# E-07_CPU_MISC.net
KiCad netlist of a schematic drawn in Altium Designer
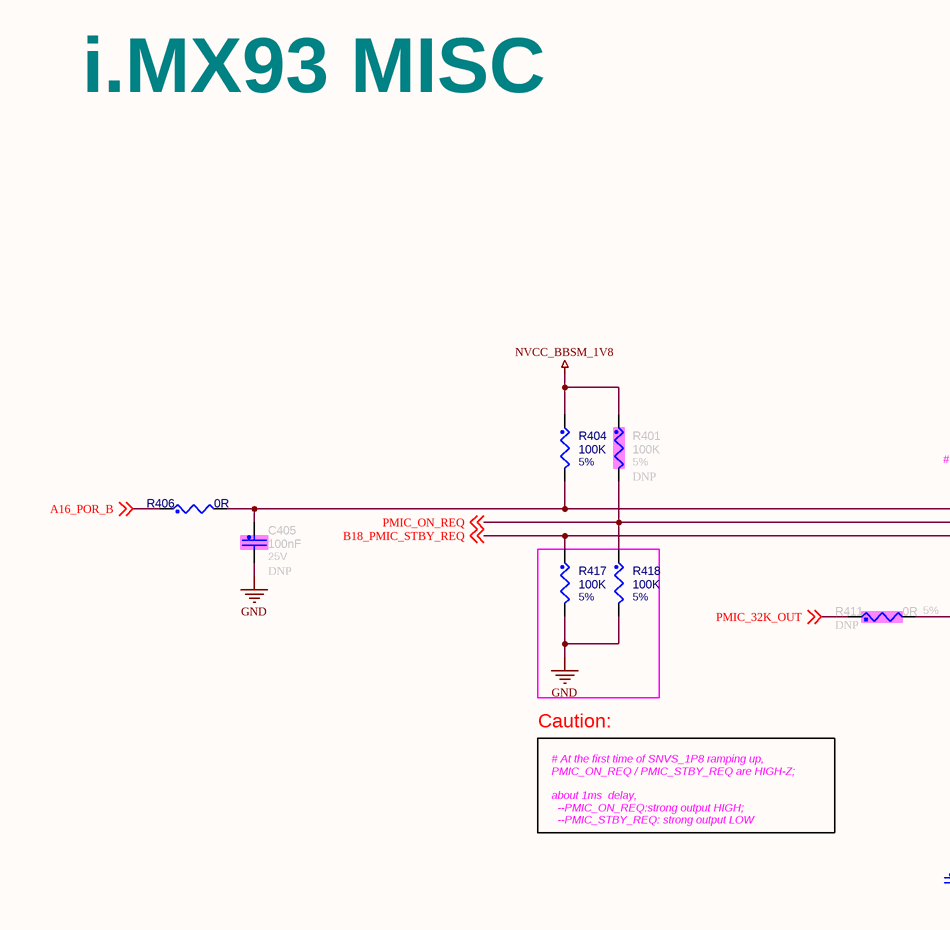
[diagram p0: E-07 CPU MISC.SchDoc, left]
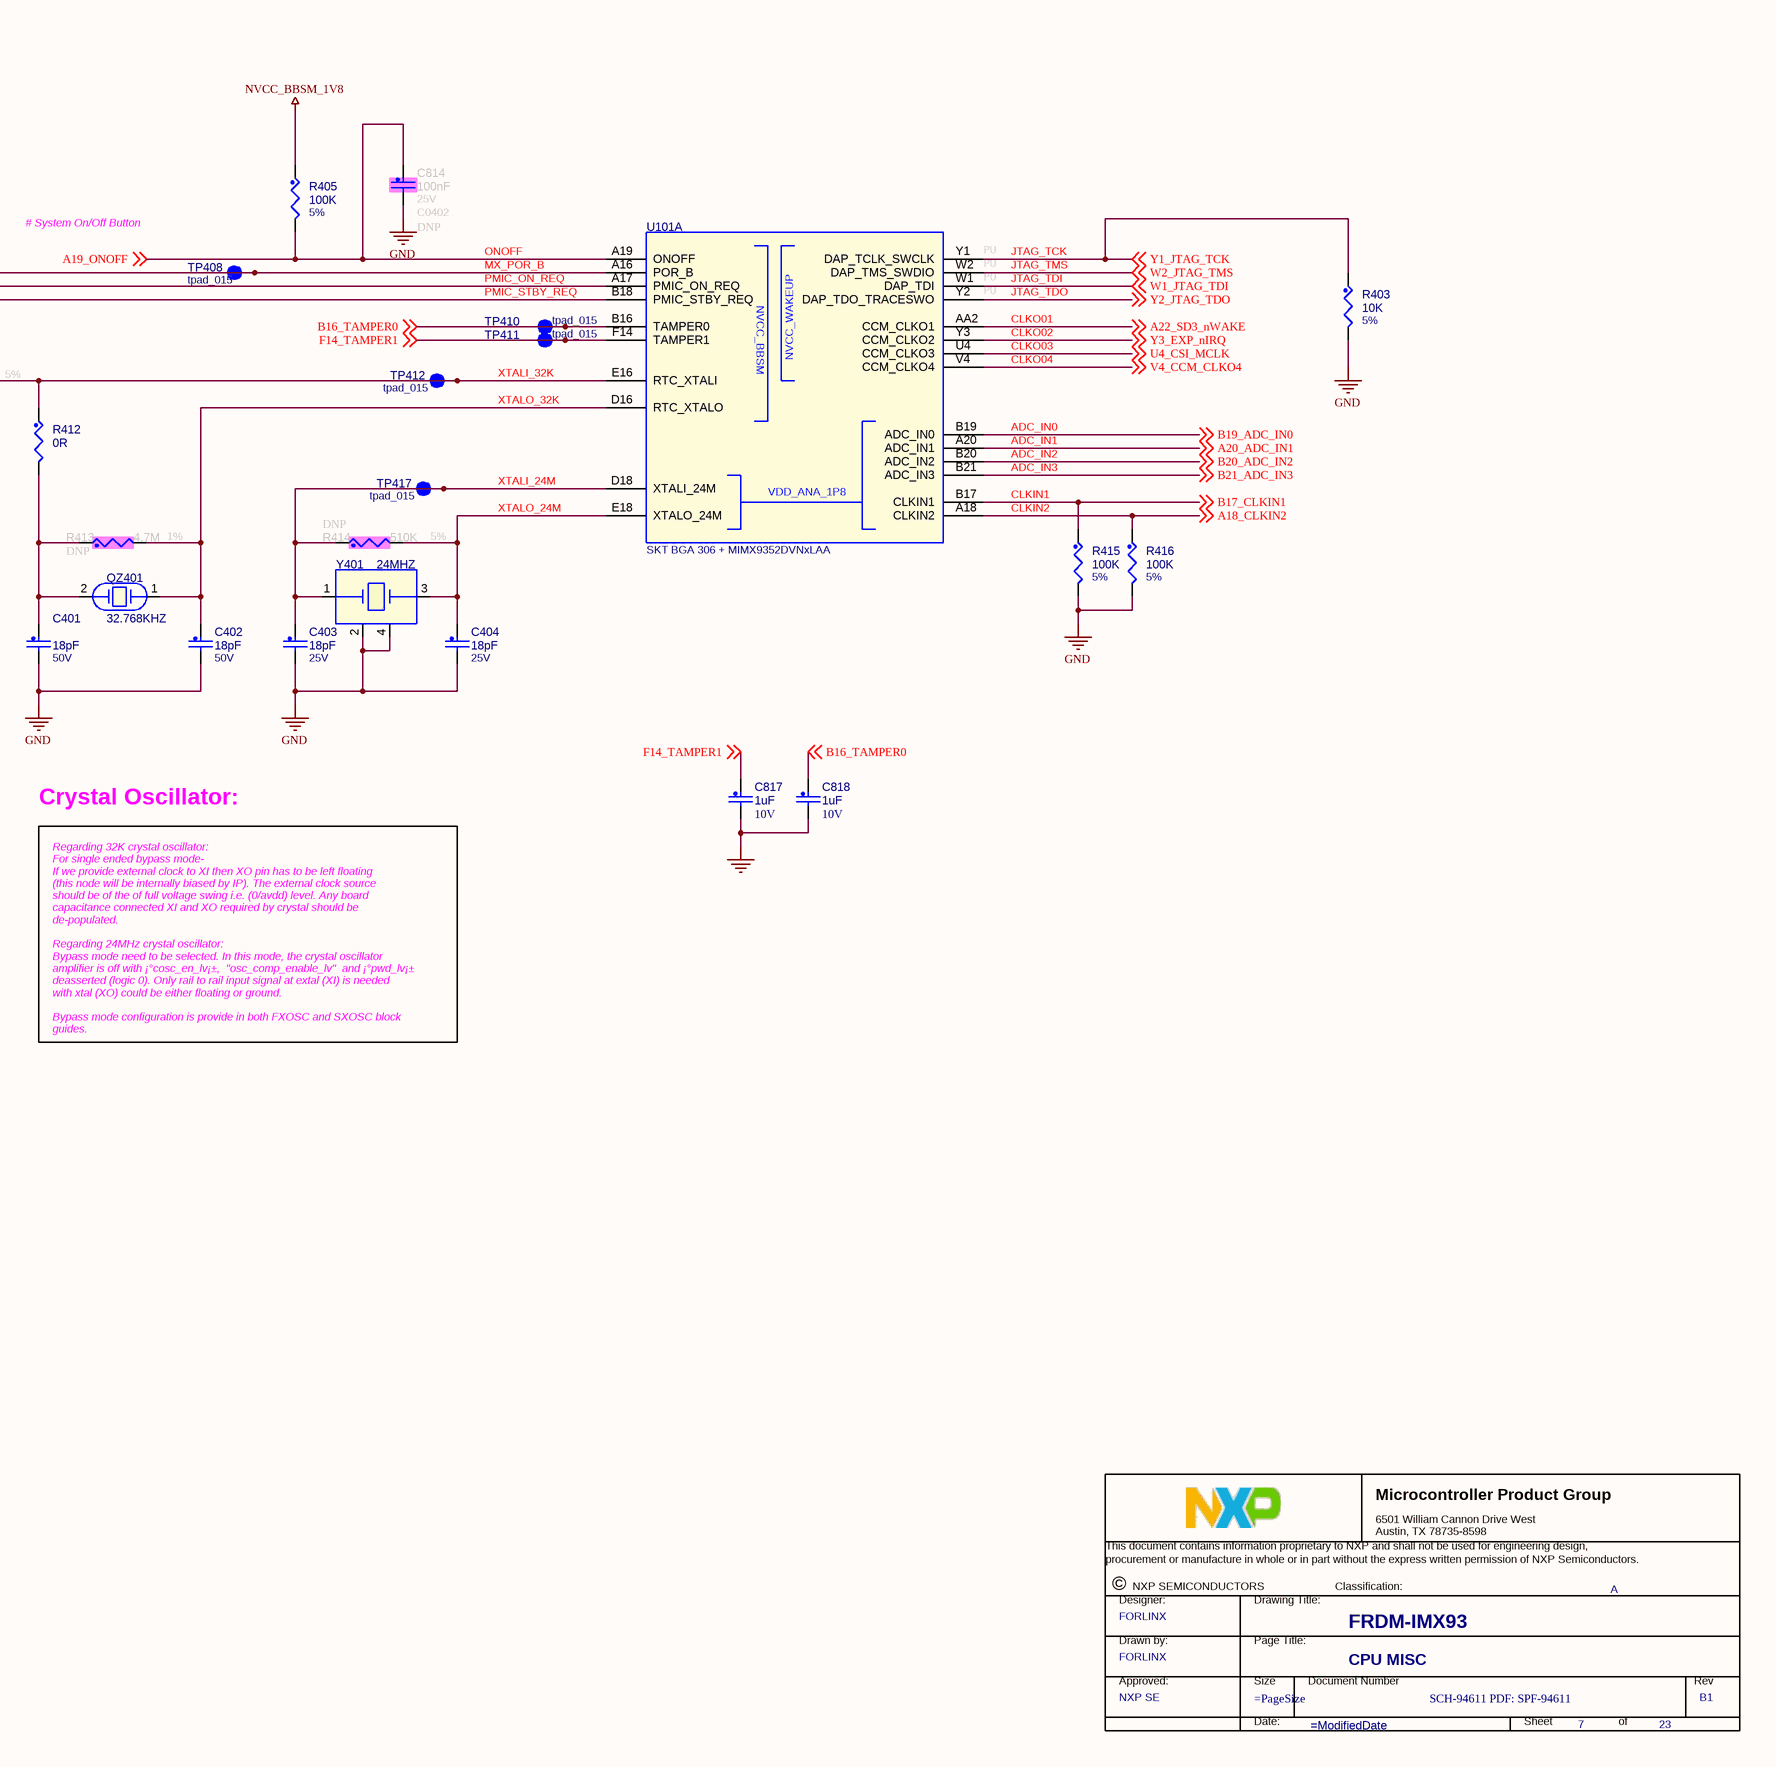
[diagram p1: E-07 CPU MISC.SchDoc, right]

(export (version "E")
  (design (tool "Eeschema 10.0.6"))
  (components
    (comp (ref "C401")
      (value "18pF")
      (footprint "C0201")
      (description "0201,18pF,50V,+/-5%,NPO")
      (fields (field (name "TOLERANCE") "5%") (field (name "VOLTAGE") "50V"))
      (libsource (lib "*") (part "CAP_NP"))
    )
    (comp (ref "C402")
      (value "18pF")
      (footprint "C0201")
      (description "0201,18pF,50V,+/-5%,NPO")
      (fields (field (name "VOLTAGE") "50V") (field (name "TOLERANCE") "5%"))
      (libsource (lib "*") (part "CAP_NP"))
    )
    (comp (ref "C403")
      (value "18pF")
      (footprint "C0201")
      (description "0201,18pF,50V,+/-5%,NPO")
      (fields (field (name "TOLERANCE") "5%") (field (name "VOLTAGE") "25V"))
      (libsource (lib "*") (part "CAP_NP"))
    )
    (comp (ref "C404")
      (value "18pF")
      (footprint "C0201")
      (description "0201,18pF,50V,+/-5%,NPO")
      (fields (field (name "TOLERANCE") "5%") (field (name "VOLTAGE") "25V"))
      (libsource (lib "*") (part "CAP_NP"))
    )
    (comp (ref "C405")
      (value "100nF")
      (footprint "C0402")
      (description "0402,100nF,50V,+/-10%,X5R")
      (fields (field (name "ASSY_OPT") "DNP") (field (name "VOLTAGE") "25V") (field (name "TOLERANCE") "10%"))
      (libsource (lib "*") (part "CAP_NP"))
    )
    (comp (ref "C814")
      (value "100nF")
      (footprint "C0402")
      (description "0402,100nF,50V,+/-10%,X5R")
      (fields
        (field (name "ASSY_OPT") "DNP")
        (field (name "TOLERANCE") "10%")
        (field (name "VOLTAGE") "25V")
        (field (name "PCB FOOTPRINT") "C0402")
      )
      (libsource (lib "*") (part "CAP_NP"))
    )
    (comp (ref "C817")
      (value "1uF")
      (footprint "C0201")
      (description "0201,1uF,10V,+/-20%,X5R")
      (fields (field (name "VOLTAGE") "10V") (field (name "TOLERANCE") "10%"))
      (libsource (lib "*") (part "CAP_NP"))
    )
    (comp (ref "C818")
      (value "1uF")
      (footprint "C0201")
      (description "0201,1uF,10V,+/-20%,X5R")
      (fields (field (name "VOLTAGE") "10V") (field (name "TOLERANCE") "10%"))
      (libsource (lib "*") (part "CAP_NP"))
    )
    (comp (ref "QZ401")
      (value "32.768KHZ")
      (footprint "XTAL2-3P2X1P5-SM")
      (description "Crystal,32.768KHZ,3.2*1.5mm,+/-20ppm,12.5PF,S999-311,-40~85+C")
      (libsource (lib "*") (part "XTAL"))
    )
    (comp (ref "R401")
      (value "100K")
      (footprint "R0402")
      (description "0402,100K,+/-1%")
      (fields (field (name "ASSY_OPT") "DNP") (field (name "VOLTAGE") "50V") (field (name "TOLERANCE") "5%"))
      (libsource (lib "*") (part "RES"))
    )
    (comp (ref "R403")
      (value "10K")
      (footprint "R0402")
      (description "0402,10K,+/-1%")
      (fields (field (name "TOLERANCE") "5%"))
      (libsource (lib "*") (part "RES"))
    )
    (comp (ref "R404")
      (value "100K")
      (footprint "R0402")
      (description "0402,100K,+/-1%")
      (fields (field (name "VOLTAGE") "50V") (field (name "TOLERANCE") "5%"))
      (libsource (lib "*") (part "RES"))
    )
    (comp (ref "R405")
      (value "100K")
      (footprint "R0402")
      (description "0402,100K,+/-1%")
      (fields (field (name "TOLERANCE") "5%") (field (name "VOLTAGE") "50V"))
      (libsource (lib "*") (part "RES"))
    )
    (comp (ref "R406")
      (value "0R")
      (footprint "R0201")
      (description "0201,0Ohm,+/-5%")
      (libsource (lib "*") (part "RES"))
    )
    (comp (ref "R411")
      (value "0R")
      (footprint "R0201")
      (description "0201,0Ohm,+/-5%")
      (fields (field (name "ASSY_OPT") "DNP") (field (name "TOLERANCE") "5%"))
      (libsource (lib "*") (part "RES"))
    )
    (comp (ref "R412")
      (value "0R")
      (footprint "R0201")
      (description "0201,0Ohm,+/-5%")
      (libsource (lib "*") (part "RES"))
    )
    (comp (ref "R413")
      (value "4.7M")
      (footprint "R0402")
      (description "0402,4.7M,+/-5%")
      (fields (field (name "ASSY_OPT") "DNP") (field (name "TOLERANCE") "1%") (field (name "VOLTAGE") "50V"))
      (libsource (lib "*") (part "RES"))
    )
    (comp (ref "R414")
      (value "510K")
      (footprint "R0402")
      (description "0402,510K,+/-5%")
      (fields (field (name "ASSY_OPT") "DNP") (field (name "TOLERANCE") "5%"))
      (libsource (lib "*") (part "RES"))
    )
    (comp (ref "R415")
      (value "100K")
      (footprint "R0402")
      (description "0402,100K,+/-1%")
      (fields (field (name "TOLERANCE") "5%") (field (name "VOLTAGE") "50V"))
      (libsource (lib "*") (part "RES"))
    )
    (comp (ref "R416")
      (value "100K")
      (footprint "R0402")
      (description "0402,100K,+/-1%")
      (fields (field (name "TOLERANCE") "5%") (field (name "VOLTAGE") "50V"))
      (libsource (lib "*") (part "RES"))
    )
    (comp (ref "R417")
      (value "100K")
      (footprint "R0402")
      (description "0402,100K,+/-1%")
      (fields (field (name "TOLERANCE") "5%") (field (name "VOLTAGE") "50V"))
      (libsource (lib "*") (part "RES"))
    )
    (comp (ref "R418")
      (value "100K")
      (footprint "R0402")
      (description "0402,100K,+/-1%")
      (fields (field (name "TOLERANCE") "5%") (field (name "VOLTAGE") "50V"))
      (libsource (lib "*") (part "RES"))
    )
    (comp (ref "TP408")
      (value "TPAD_015")
      (footprint "tpad_015")
      (description "no part to order")
      (fields (field (name "PCB FOOTPRINT") "tpad_015"))
      (libsource (lib "*") (part "TESTLOOP"))
    )
    (comp (ref "TP410")
      (value "TPAD_015")
      (footprint "tpad_015")
      (description "no part to order")
      (fields (field (name "PCB FOOTPRINT") "tpad_015"))
      (libsource (lib "*") (part "TESTLOOP"))
    )
    (comp (ref "TP411")
      (value "TPAD_015")
      (footprint "tpad_015")
      (description "no part to order")
      (fields (field (name "PCB FOOTPRINT") "tpad_015"))
      (libsource (lib "*") (part "TESTLOOP"))
    )
    (comp (ref "TP412")
      (value "TPAD_015")
      (footprint "tpad_015")
      (description "no part to order")
      (fields (field (name "PCB FOOTPRINT") "tpad_015"))
      (libsource (lib "*") (part "TESTLOOP"))
    )
    (comp (ref "TP417")
      (value "TPAD_015")
      (footprint "tpad_015")
      (description "no part to order")
      (fields (field (name "PCB FOOTPRINT") "tpad_015"))
      (libsource (lib "*") (part "TESTLOOP"))
    )
    (comp (ref "U101")
      (value "SKT BGA 306 + MIMX9352DVNxLAA")
      (footprint "skt_bga306_0p5_sq16p23_elast_nsp")
      (description "MIMX9352CVVXMAB,-40~105+C,11*11mm,0.5mm pitch,FCBGA,A,306pin,1.7GHz")
      (libsource (lib "*") (part "MIMX9352DVNxLAA"))
    )
    (comp (ref "Y401")
      (value "24MHZ")
      (footprint "xtlosc4_3p2x2p5mm_sm")
      (description "Crystal,24MHZ,4P,3.2*2.5mm,+/-20ppm,12pF")
      (libsource (lib "*") (part "XTAL_13"))
    )
  )
  (nets
    (net (code "1") (name "/MX_POR_B") (class "Default")
      (node (ref "C405") (pin "1") (pinfunction "1_1") (pintype "passive"))
      (node (ref "R404") (pin "2") (pinfunction "2_2") (pintype "passive"))
      (node (ref "R406") (pin "2") (pinfunction "2_2") (pintype "passive"))
      (node (ref "TP408") (pin "1") (pinfunction "Pin1_1") (pintype "passive"))
      (node (ref "U101") (pin "A16") (pinfunction "POR_B_A16") (pintype "passive"))
    )
    (net (code "2") (name "/XTALI_24M") (class "Default")
      (node (ref "C403") (pin "1") (pinfunction "1_1") (pintype "passive"))
      (node (ref "R414") (pin "1") (pinfunction "1_1") (pintype "passive"))
      (node (ref "TP417") (pin "1") (pinfunction "Pin1_1") (pintype "passive"))
      (node (ref "U101") (pin "D18") (pinfunction "XTALI_24M_D18") (pintype "passive"))
      (node (ref "Y401") (pin "1") (pinfunction "1_1") (pintype "passive"))
    )
    (net (code "3") (name "/XTALI_32K") (class "Default")
      (node (ref "R411") (pin "2") (pinfunction "2_2") (pintype "passive"))
      (node (ref "R412") (pin "1") (pinfunction "1_1") (pintype "passive"))
      (node (ref "TP412") (pin "1") (pinfunction "Pin1_1") (pintype "passive"))
      (node (ref "U101") (pin "E16") (pinfunction "RTC_XTALI_E16") (pintype "passive"))
    )
    (net (code "4") (name "/XTALO_24M") (class "Default")
      (node (ref "C404") (pin "1") (pinfunction "1_1") (pintype "passive"))
      (node (ref "R414") (pin "2") (pinfunction "2_2") (pintype "passive"))
      (node (ref "U101") (pin "E18") (pinfunction "XTALO_24M_E18") (pintype "passive"))
      (node (ref "Y401") (pin "3") (pinfunction "3_3") (pintype "passive"))
    )
    (net (code "5") (name "/XTALO_32K") (class "Default")
      (node (ref "C402") (pin "1") (pinfunction "1_1") (pintype "passive"))
      (node (ref "QZ401") (pin "1") (pinfunction "1_1") (pintype "passive"))
      (node (ref "R413") (pin "2") (pinfunction "2_2") (pintype "passive"))
      (node (ref "U101") (pin "D16") (pinfunction "RTC_XTALO_D16") (pintype "passive"))
    )
    (net (code "6") (name "A16_POR_B") (class "Default")
      (node (ref "R406") (pin "1") (pinfunction "1_1") (pintype "passive"))
    )
    (net (code "7") (name "A18_CLKIN2") (class "Default")
      (node (ref "R416") (pin "1") (pinfunction "1_1") (pintype "passive"))
      (node (ref "U101") (pin "A18") (pinfunction "CLKIN2_A18") (pintype "passive"))
    )
    (net (code "8") (name "A19_ONOFF") (class "Default")
      (node (ref "C814") (pin "1") (pinfunction "1_1") (pintype "passive"))
      (node (ref "R405") (pin "2") (pinfunction "2_2") (pintype "passive"))
      (node (ref "U101") (pin "A19") (pinfunction "ONOFF_A19") (pintype "passive"))
    )
    (net (code "9") (name "A20_ADC_IN1") (class "Default")
      (node (ref "U101") (pin "A20") (pinfunction "ADC_IN1_A20") (pintype "passive"))
    )
    (net (code "10") (name "A22_SD3_nWAKE") (class "Default")
      (node (ref "U101") (pin "AA2") (pinfunction "CCM_CLKO1_AA2") (pintype "passive"))
    )
    (net (code "11") (name "B16_TAMPER0") (class "Default")
      (node (ref "C818") (pin "1") (pinfunction "1_1") (pintype "passive"))
      (node (ref "TP410") (pin "1") (pinfunction "Pin1_1") (pintype "passive"))
      (node (ref "U101") (pin "B16") (pinfunction "TAMPER0_B16") (pintype "passive"))
    )
    (net (code "12") (name "B17_CLKIN1") (class "Default")
      (node (ref "R415") (pin "1") (pinfunction "1_1") (pintype "passive"))
      (node (ref "U101") (pin "B17") (pinfunction "CLKIN1_B17") (pintype "passive"))
    )
    (net (code "13") (name "B18_PMIC_STBY_REQ") (class "Default")
      (node (ref "R417") (pin "1") (pinfunction "1_1") (pintype "passive"))
      (node (ref "U101") (pin "B18") (pinfunction "PMIC_STBY_REQ_B18") (pintype "passive"))
    )
    (net (code "14") (name "B19_ADC_IN0") (class "Default")
      (node (ref "U101") (pin "B19") (pinfunction "ADC_IN0_B19") (pintype "passive"))
    )
    (net (code "15") (name "B20_ADC_IN2") (class "Default")
      (node (ref "U101") (pin "B20") (pinfunction "ADC_IN2_B20") (pintype "passive"))
    )
    (net (code "16") (name "B21_ADC_IN3") (class "Default")
      (node (ref "U101") (pin "B21") (pinfunction "ADC_IN3_B21") (pintype "passive"))
    )
    (net (code "17") (name "F14_TAMPER1") (class "Default")
      (node (ref "C817") (pin "1") (pinfunction "1_1") (pintype "passive"))
      (node (ref "TP411") (pin "1") (pinfunction "Pin1_1") (pintype "passive"))
      (node (ref "U101") (pin "F14") (pinfunction "TAMPER1_F14") (pintype "passive"))
    )
    (net (code "18") (name "GND") (class "Default")
      (node (ref "C401") (pin "2") (pinfunction "2_2") (pintype "passive"))
      (node (ref "C402") (pin "2") (pinfunction "2_2") (pintype "passive"))
      (node (ref "C403") (pin "2") (pinfunction "2_2") (pintype "passive"))
      (node (ref "C404") (pin "2") (pinfunction "2_2") (pintype "passive"))
      (node (ref "C405") (pin "2") (pinfunction "2_2") (pintype "passive"))
      (node (ref "C814") (pin "2") (pinfunction "2_2") (pintype "passive"))
      (node (ref "C817") (pin "2") (pinfunction "2_2") (pintype "passive"))
      (node (ref "C818") (pin "2") (pinfunction "2_2") (pintype "passive"))
      (node (ref "R403") (pin "2") (pinfunction "2_2") (pintype "passive"))
      (node (ref "R415") (pin "2") (pinfunction "2_2") (pintype "passive"))
      (node (ref "R416") (pin "2") (pinfunction "2_2") (pintype "passive"))
      (node (ref "R417") (pin "2") (pinfunction "2_2") (pintype "passive"))
      (node (ref "R418") (pin "2") (pinfunction "2_2") (pintype "passive"))
      (node (ref "Y401") (pin "2") (pinfunction "2_2") (pintype "passive"))
      (node (ref "Y401") (pin "4") (pinfunction "4_4") (pintype "passive"))
    )
    (net (code "19") (name "NVCC_BBSM_1V8") (class "Default")
      (node (ref "R401") (pin "1") (pinfunction "1_1") (pintype "passive"))
      (node (ref "R404") (pin "1") (pinfunction "1_1") (pintype "passive"))
      (node (ref "R405") (pin "1") (pinfunction "1_1") (pintype "passive"))
    )
    (net (code "20") (name "Net-(C401-Pad1)") (class "Default")
      (node (ref "C401") (pin "1") (pinfunction "1_1") (pintype "passive"))
      (node (ref "QZ401") (pin "2") (pinfunction "2_2") (pintype "passive"))
      (node (ref "R412") (pin "2") (pinfunction "2_2") (pintype "passive"))
      (node (ref "R413") (pin "1") (pinfunction "1_1") (pintype "passive"))
    )
    (net (code "21") (name "PMIC_32K_OUT") (class "Default")
      (node (ref "R411") (pin "1") (pinfunction "1_1") (pintype "passive"))
    )
    (net (code "22") (name "PMIC_ON_REQ") (class "Default")
      (node (ref "R401") (pin "2") (pinfunction "2_2") (pintype "passive"))
      (node (ref "R418") (pin "1") (pinfunction "1_1") (pintype "passive"))
      (node (ref "U101") (pin "A17") (pinfunction "PMIC_ON_REQ_A17") (pintype "passive"))
    )
    (net (code "23") (name "U4_CSI_MCLK") (class "Default")
      (node (ref "U101") (pin "U4") (pinfunction "CCM_CLKO3_U4") (pintype "passive"))
    )
    (net (code "24") (name "V4_CCM_CLKO4") (class "Default")
      (node (ref "U101") (pin "V4") (pinfunction "CCM_CLKO4_V4") (pintype "passive"))
    )
    (net (code "25") (name "W1_JTAG_TDI") (class "Default")
      (node (ref "U101") (pin "W1") (pinfunction "DAP_TDI_W1") (pintype "passive"))
    )
    (net (code "26") (name "W2_JTAG_TMS") (class "Default")
      (node (ref "U101") (pin "W2") (pinfunction "DAP_TMS_SWDIO_W2") (pintype "passive"))
    )
    (net (code "27") (name "Y1_JTAG_TCK") (class "Default")
      (node (ref "R403") (pin "1") (pinfunction "1_1") (pintype "passive"))
      (node (ref "U101") (pin "Y1") (pinfunction "DAP_TCLK_SWCLK_Y1") (pintype "passive"))
    )
    (net (code "28") (name "Y2_JTAG_TDO") (class "Default")
      (node (ref "U101") (pin "Y2") (pinfunction "DAP_TDO_TRACESWO_Y2") (pintype "passive"))
    )
    (net (code "29") (name "Y3_EXP_nIRQ") (class "Default")
      (node (ref "U101") (pin "Y3") (pinfunction "CCM_CLKO2_Y3") (pintype "passive"))
    )
  )
)
